# SCH_Meshtastic_FakeTec_PCB_2025-07-15.net
KiCad netlist of a schematic drawn in EasyEDA
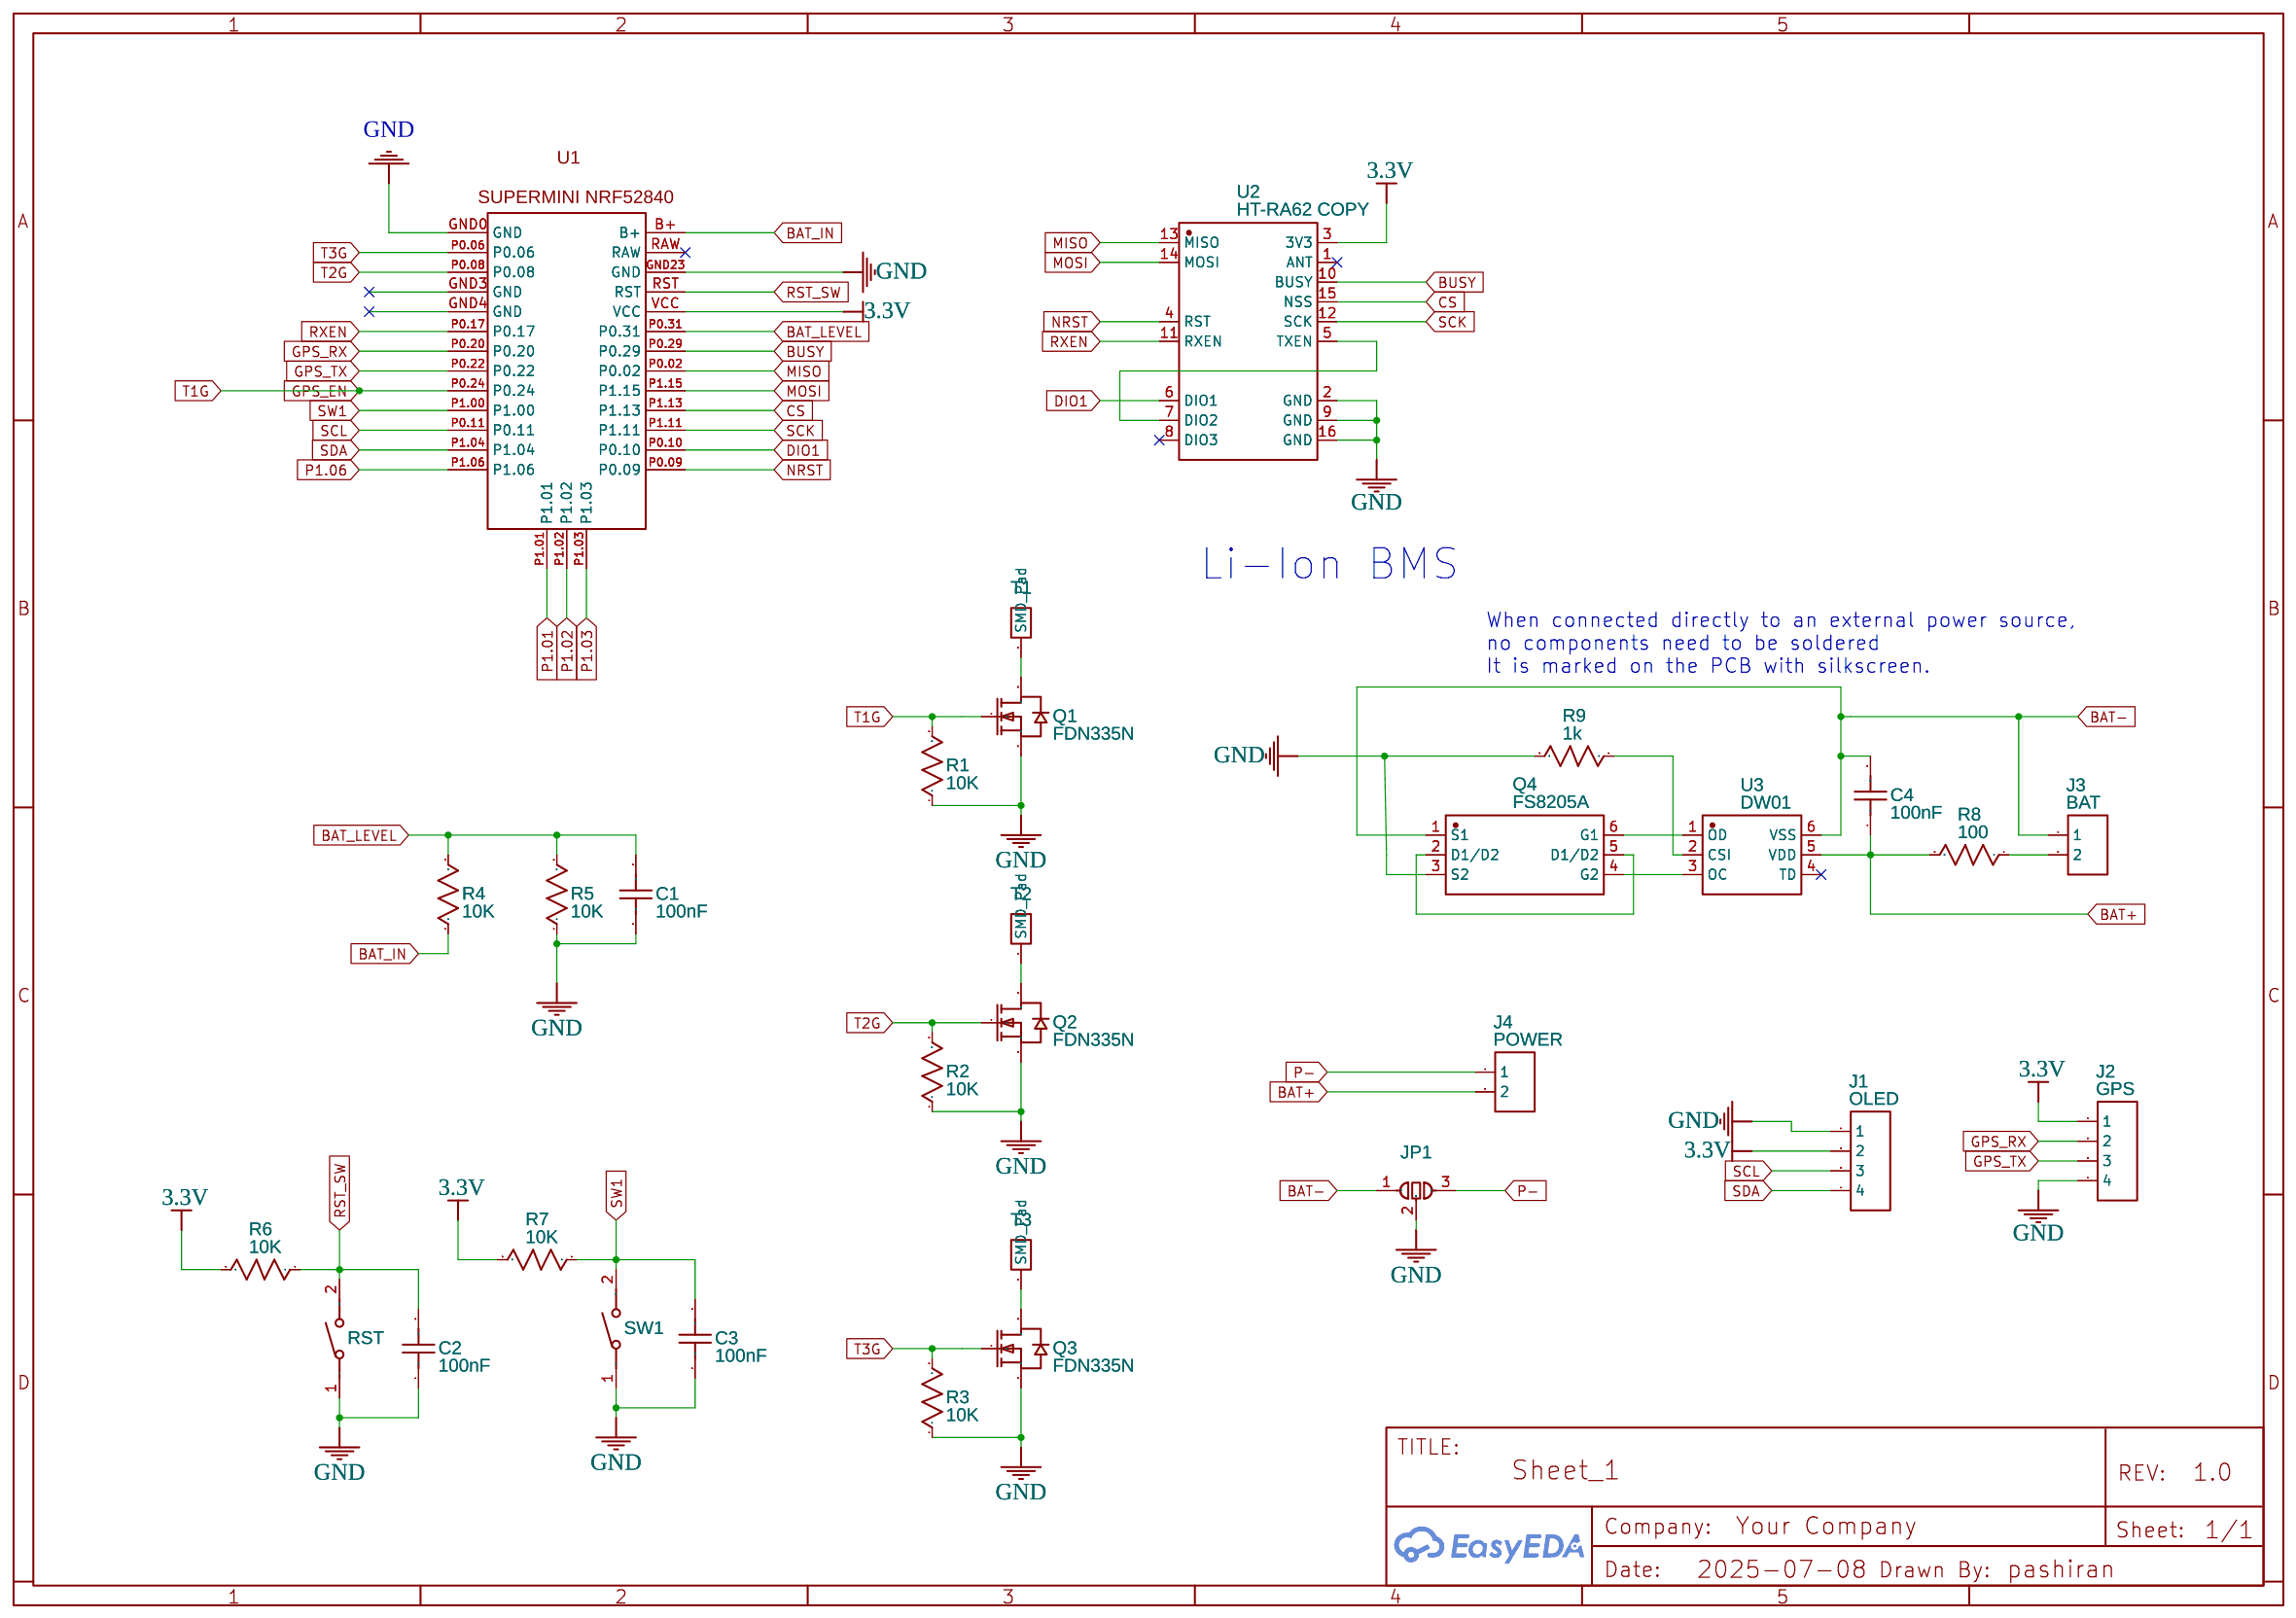
[diagram p0: schematic sheet]

(export (version "E")
  (design (tool "Eeschema 10.0.6"))
  (components
    (comp (ref "C1") (value "100nF") (libsource (lib "") (part "C_0805_US")))
    (comp (ref "C2") (value "100nF") (libsource (lib "") (part "C_0805_US")))
    (comp (ref "C3") (value "100nF") (libsource (lib "") (part "C_0805_US")))
    (comp (ref "C4") (value "100nF") (libsource (lib "") (part "C_0805_US")))
    (comp (ref "J1") (value "OLED") (libsource (lib "") (part "HDR-M-2.54_1x4")))
    (comp (ref "J2") (value "GPS") (libsource (lib "") (part "HDR-M-2.54_1x4")))
    (comp (ref "J3") (value "BAT") (libsource (lib "") (part "HDR-M-2.54_1x2")))
    (comp (ref "J4") (value "POWER") (libsource (lib "") (part "HDR-M-2.54_1x2")))
    (comp (ref "JP1") (value "SOLDERJUMPER_3") (libsource (lib "") (part "SOLDERJUMPER_3")))
    (comp (ref "Q1")
      (value "FDN335N")
      (fields (field (name "Manufacturer") "TECH PUBLIC(台舟)"))
      (libsource (lib "") (part "FDN335N_C5123904"))
    )
    (comp (ref "Q2")
      (value "FDN335N")
      (fields (field (name "Manufacturer") "TECH PUBLIC(台舟)"))
      (libsource (lib "") (part "FDN335N_C5123904"))
    )
    (comp (ref "Q3")
      (value "FDN335N")
      (fields (field (name "Manufacturer") "TECH PUBLIC(台舟)"))
      (libsource (lib "") (part "FDN335N_C5123904"))
    )
    (comp (ref "Q4")
      (value "FS8205A")
      (fields (field (name "Manufacturer") "TECH PUBLIC(台舟)"))
      (libsource (lib "") (part "FS8205A_C2830320"))
    )
    (comp (ref "R1") (value "10K") (libsource (lib "") (part "R_0805_US")))
    (comp (ref "R2") (value "10K") (libsource (lib "") (part "R_0805_US")))
    (comp (ref "R3") (value "10K") (libsource (lib "") (part "R_0805_US")))
    (comp (ref "R4") (value "10K") (libsource (lib "") (part "R_0805_US")))
    (comp (ref "R5") (value "10K") (libsource (lib "") (part "R_0805_US")))
    (comp (ref "R6") (value "10K") (libsource (lib "") (part "R_0805_US_1")))
    (comp (ref "R7") (value "10K") (libsource (lib "") (part "R_0805_US_1")))
    (comp (ref "R8") (value "100") (libsource (lib "") (part "R_0805_US_1")))
    (comp (ref "R9") (value "1k") (libsource (lib "") (part "R_0805_US_1")))
    (comp (ref "RST")
      (value "TS-1088-AR02016")
      (fields (field (name "Manufacturer") "XUNPU(讯普)"))
      (libsource (lib "") (part "TS-1088-AR02016_1"))
    )
    (comp (ref "SW1")
      (value "TS-1088-AR02016")
      (fields (field (name "Manufacturer") "XUNPU(讯普)"))
      (libsource (lib "") (part "TS-1088-AR02016"))
    )
    (comp (ref "T1") (value "SMD_PAD") (libsource (lib "") (part "SMD_PAD")))
    (comp (ref "T2") (value "SMD_PAD") (libsource (lib "") (part "SMD_PAD")))
    (comp (ref "T3") (value "SMD_PAD") (libsource (lib "") (part "SMD_PAD")))
    (comp (ref "U1") (value "SUPERMINI_NRF52840 COPY") (libsource (lib "") (part "SUPERMINI_NRF52840 COPY")))
    (comp (ref "U2")
      (value "HT-RA62 COPY")
      (fields (field (name "Manufacturer Part") "HT-RA62"))
      (libsource (lib "") (part "HT-RA62 COPY"))
    )
    (comp (ref "U3")
      (value "DW01")
      (fields (field (name "Manufacturer") "JSMSEMI(杰盛微)"))
      (libsource (lib "") (part "DW01_C917079"))
    )
  )
  (nets
    (net (code "1") (name "3.3V") (class "Default")
      (node (ref "J1") (pin "2") (pinfunction "2_2") (pintype "unspecified"))
      (node (ref "J2") (pin "1") (pinfunction "1_1") (pintype "unspecified"))
      (node (ref "R6") (pin "2") (pinfunction "2_2") (pintype "unspecified"))
      (node (ref "R7") (pin "2") (pinfunction "2_2") (pintype "unspecified"))
      (node (ref "U1") (pin "VCC") (pinfunction "VCC_VCC") (pintype "bidirectional"))
      (node (ref "U2") (pin "3") (pinfunction "3V3_3") (pintype "unspecified"))
    )
    (net (code "2") (name "BAT+") (class "Default")
      (node (ref "C4") (pin "1") (pinfunction "1_1") (pintype "unspecified"))
      (node (ref "J4") (pin "2") (pinfunction "2_2") (pintype "unspecified"))
      (node (ref "R8") (pin "2") (pinfunction "2_2") (pintype "unspecified"))
      (node (ref "U3") (pin "5") (pinfunction "VDD_5") (pintype "unspecified"))
    )
    (net (code "3") (name "BAT-") (class "Default")
      (node (ref "C4") (pin "2") (pinfunction "2_2") (pintype "unspecified"))
      (node (ref "J3") (pin "1") (pinfunction "1_1") (pintype "unspecified"))
      (node (ref "JP1") (pin "1") (pinfunction "A_1") (pintype "unspecified"))
      (node (ref "Q4") (pin "1") (pinfunction "S1_1") (pintype "unspecified"))
      (node (ref "U3") (pin "6") (pinfunction "VSS_6") (pintype "unspecified"))
    )
    (net (code "4") (name "BAT_IN") (class "Default")
      (node (ref "R4") (pin "1") (pinfunction "1_1") (pintype "unspecified"))
      (node (ref "U1") (pin "B+") (pinfunction "B+_B+") (pintype "bidirectional"))
    )
    (net (code "5") (name "BAT_LEVEL") (class "Default")
      (node (ref "C1") (pin "2") (pinfunction "2_2") (pintype "unspecified"))
      (node (ref "R4") (pin "2") (pinfunction "2_2") (pintype "unspecified"))
      (node (ref "R5") (pin "2") (pinfunction "2_2") (pintype "unspecified"))
      (node (ref "U1") (pin "P0.31") (pinfunction "P0.31_P0.31") (pintype "bidirectional"))
    )
    (net (code "6") (name "BUSY") (class "Default")
      (node (ref "U1") (pin "P0.29") (pinfunction "P0.29_P0.29") (pintype "bidirectional"))
      (node (ref "U2") (pin "10") (pinfunction "BUSY_10") (pintype "unspecified"))
    )
    (net (code "7") (name "CS") (class "Default")
      (node (ref "U1") (pin "P1.13") (pinfunction "P1.13_P1.13") (pintype "bidirectional"))
      (node (ref "U2") (pin "15") (pinfunction "NSS_15") (pintype "unspecified"))
    )
    (net (code "8") (name "DIO1") (class "Default")
      (node (ref "U1") (pin "P0.10") (pinfunction "P0.10_P0.10") (pintype "bidirectional"))
      (node (ref "U2") (pin "6") (pinfunction "DIO1_6") (pintype "unspecified"))
    )
    (net (code "9") (name "GND") (class "Default")
      (node (ref "C1") (pin "1") (pinfunction "1_1") (pintype "unspecified"))
      (node (ref "C2") (pin "1") (pinfunction "1_1") (pintype "unspecified"))
      (node (ref "C3") (pin "1") (pinfunction "1_1") (pintype "unspecified"))
      (node (ref "J1") (pin "1") (pinfunction "1_1") (pintype "unspecified"))
      (node (ref "J2") (pin "4") (pinfunction "4_4") (pintype "unspecified"))
      (node (ref "JP1") (pin "2") (pinfunction "C_2") (pintype "unspecified"))
      (node (ref "Q1") (pin "2") (pinfunction "S_2") (pintype "unspecified"))
      (node (ref "Q2") (pin "2") (pinfunction "S_2") (pintype "unspecified"))
      (node (ref "Q3") (pin "2") (pinfunction "S_2") (pintype "unspecified"))
      (node (ref "Q4") (pin "3") (pinfunction "S2_3") (pintype "unspecified"))
      (node (ref "R1") (pin "1") (pinfunction "1_1") (pintype "unspecified"))
      (node (ref "R2") (pin "1") (pinfunction "1_1") (pintype "unspecified"))
      (node (ref "R3") (pin "1") (pinfunction "1_1") (pintype "unspecified"))
      (node (ref "R5") (pin "1") (pinfunction "1_1") (pintype "unspecified"))
      (node (ref "R9") (pin "2") (pinfunction "2_2") (pintype "unspecified"))
      (node (ref "RST") (pin "1") (pinfunction "1_1") (pintype "unspecified"))
      (node (ref "SW1") (pin "1") (pinfunction "1_1") (pintype "unspecified"))
      (node (ref "U1") (pin "GND0") (pinfunction "GND_GND0") (pintype "unspecified"))
      (node (ref "U1") (pin "GND23") (pinfunction "GND_GND23") (pintype "bidirectional"))
      (node (ref "U2") (pin "16") (pinfunction "GND_16") (pintype "unspecified"))
      (node (ref "U2") (pin "2") (pinfunction "GND_2") (pintype "unspecified"))
      (node (ref "U2") (pin "9") (pinfunction "GND_9") (pintype "unspecified"))
    )
    (net (code "10") (name "GPS_EN") (class "Default")
      (node (ref "Q1") (pin "1") (pinfunction "G_1") (pintype "unspecified"))
      (node (ref "R1") (pin "2") (pinfunction "2_2") (pintype "unspecified"))
      (node (ref "U1") (pin "P0.24") (pinfunction "P0.24_P0.24") (pintype "unspecified"))
    )
    (net (code "11") (name "GPS_RX") (class "Default")
      (node (ref "J2") (pin "2") (pinfunction "2_2") (pintype "unspecified"))
      (node (ref "U1") (pin "P0.20") (pinfunction "P0.20_P0.20") (pintype "unspecified"))
    )
    (net (code "12") (name "GPS_TX") (class "Default")
      (node (ref "J2") (pin "3") (pinfunction "3_3") (pintype "unspecified"))
      (node (ref "U1") (pin "P0.22") (pinfunction "P0.22_P0.22") (pintype "unspecified"))
    )
    (net (code "13") (name "MISO") (class "Default")
      (node (ref "U1") (pin "P0.02") (pinfunction "P0.02_P0.02") (pintype "bidirectional"))
      (node (ref "U2") (pin "13") (pinfunction "MISO_13") (pintype "unspecified"))
    )
    (net (code "14") (name "MOSI") (class "Default")
      (node (ref "U1") (pin "P1.15") (pinfunction "P1.15_P1.15") (pintype "bidirectional"))
      (node (ref "U2") (pin "14") (pinfunction "MOSI_14") (pintype "unspecified"))
    )
    (net (code "15") (name "NRST") (class "Default")
      (node (ref "U1") (pin "P0.09") (pinfunction "P0.09_P0.09") (pintype "bidirectional"))
      (node (ref "U2") (pin "4") (pinfunction "RST_4") (pintype "unspecified"))
    )
    (net (code "16") (name "Net-(J3-Pad2)") (class "Default")
      (node (ref "J3") (pin "2") (pinfunction "2_2") (pintype "unspecified"))
      (node (ref "R8") (pin "1") (pinfunction "1_1") (pintype "unspecified"))
    )
    (net (code "17") (name "Net-(Q1-D)") (class "Default")
      (node (ref "Q1") (pin "3") (pinfunction "D_3") (pintype "unspecified"))
      (node (ref "T1") (pin "1") (pinfunction "SMD_Pad_1") (pintype "unspecified"))
    )
    (net (code "18") (name "Net-(Q2-D)") (class "Default")
      (node (ref "Q2") (pin "3") (pinfunction "D_3") (pintype "unspecified"))
      (node (ref "T2") (pin "1") (pinfunction "SMD_Pad_1") (pintype "unspecified"))
    )
    (net (code "19") (name "Net-(Q3-D)") (class "Default")
      (node (ref "Q3") (pin "3") (pinfunction "D_3") (pintype "unspecified"))
      (node (ref "T3") (pin "1") (pinfunction "SMD_Pad_1") (pintype "unspecified"))
    )
    (net (code "20") (name "Net-(Q4-D1{slash}D2-Pad2)") (class "Default")
      (node (ref "Q4") (pin "2") (pinfunction "D1/D2_2") (pintype "unspecified"))
      (node (ref "Q4") (pin "5") (pinfunction "D1/D2_5") (pintype "unspecified"))
    )
    (net (code "21") (name "Net-(Q4-G1)") (class "Default")
      (node (ref "Q4") (pin "6") (pinfunction "G1_6") (pintype "unspecified"))
      (node (ref "U3") (pin "1") (pinfunction "OD_1") (pintype "unspecified"))
    )
    (net (code "22") (name "Net-(Q4-G2)") (class "Default")
      (node (ref "Q4") (pin "4") (pinfunction "G2_4") (pintype "unspecified"))
      (node (ref "U3") (pin "3") (pinfunction "OC_3") (pintype "unspecified"))
    )
    (net (code "23") (name "Net-(U2-DIO2)") (class "Default")
      (node (ref "U2") (pin "5") (pinfunction "TXEN_5") (pintype "unspecified"))
      (node (ref "U2") (pin "7") (pinfunction "DIO2_7") (pintype "unspecified"))
    )
    (net (code "24") (name "Net-(U3-CSI)") (class "Default")
      (node (ref "R9") (pin "1") (pinfunction "1_1") (pintype "unspecified"))
      (node (ref "U3") (pin "2") (pinfunction "CSI_2") (pintype "unspecified"))
    )
    (net (code "25") (name "P-") (class "Default")
      (node (ref "J4") (pin "1") (pinfunction "1_1") (pintype "unspecified"))
      (node (ref "JP1") (pin "3") (pinfunction "B_3") (pintype "unspecified"))
    )
    (net (code "26") (name "P1.01") (class "Default")
      (node (ref "U1") (pin "P1.01") (pinfunction "P1.01_P1.01") (pintype "unspecified"))
    )
    (net (code "27") (name "P1.02") (class "Default")
      (node (ref "U1") (pin "P1.02") (pinfunction "P1.02_P1.02") (pintype "unspecified"))
    )
    (net (code "28") (name "P1.03") (class "Default")
      (node (ref "U1") (pin "P1.03") (pinfunction "P1.03_P1.03") (pintype "unspecified"))
    )
    (net (code "29") (name "P1.06") (class "Default")
      (node (ref "U1") (pin "P1.06") (pinfunction "P1.06_P1.06") (pintype "unspecified"))
    )
    (net (code "30") (name "RST_SW") (class "Default")
      (node (ref "C2") (pin "2") (pinfunction "2_2") (pintype "unspecified"))
      (node (ref "R6") (pin "1") (pinfunction "1_1") (pintype "unspecified"))
      (node (ref "RST") (pin "2") (pinfunction "2_2") (pintype "unspecified"))
      (node (ref "U1") (pin "RST") (pinfunction "RST_RST") (pintype "bidirectional"))
    )
    (net (code "31") (name "RXEN") (class "Default")
      (node (ref "U1") (pin "P0.17") (pinfunction "P0.17_P0.17") (pintype "unspecified"))
      (node (ref "U2") (pin "11") (pinfunction "RXEN_11") (pintype "unspecified"))
    )
    (net (code "32") (name "SCK") (class "Default")
      (node (ref "U1") (pin "P1.11") (pinfunction "P1.11_P1.11") (pintype "bidirectional"))
      (node (ref "U2") (pin "12") (pinfunction "SCK_12") (pintype "unspecified"))
    )
    (net (code "33") (name "SCL") (class "Default")
      (node (ref "J1") (pin "3") (pinfunction "3_3") (pintype "unspecified"))
      (node (ref "U1") (pin "P0.11") (pinfunction "P0.11_P0.11") (pintype "unspecified"))
    )
    (net (code "34") (name "SDA") (class "Default")
      (node (ref "J1") (pin "4") (pinfunction "4_4") (pintype "unspecified"))
      (node (ref "U1") (pin "P1.04") (pinfunction "P1.04_P1.04") (pintype "unspecified"))
    )
    (net (code "35") (name "SW1") (class "Default")
      (node (ref "C3") (pin "2") (pinfunction "2_2") (pintype "unspecified"))
      (node (ref "R7") (pin "1") (pinfunction "1_1") (pintype "unspecified"))
      (node (ref "SW1") (pin "2") (pinfunction "2_2") (pintype "unspecified"))
      (node (ref "U1") (pin "P1.00") (pinfunction "P1.00_P1.00") (pintype "unspecified"))
    )
    (net (code "36") (name "T2G") (class "Default")
      (node (ref "Q2") (pin "1") (pinfunction "G_1") (pintype "unspecified"))
      (node (ref "R2") (pin "2") (pinfunction "2_2") (pintype "unspecified"))
      (node (ref "U1") (pin "P0.08") (pinfunction "P0.08_P0.08") (pintype "input"))
    )
    (net (code "37") (name "T3G") (class "Default")
      (node (ref "Q3") (pin "1") (pinfunction "G_1") (pintype "unspecified"))
      (node (ref "R3") (pin "2") (pinfunction "2_2") (pintype "unspecified"))
      (node (ref "U1") (pin "P0.06") (pinfunction "P0.06_P0.06") (pintype "unspecified"))
    )
    (net (code "38") (name "unconnected-(U1-GND-PadGND3)") (class "Default")
      (node (ref "U1") (pin "GND3") (pinfunction "GND_GND3") (pintype "unspecified+no_connect"))
    )
    (net (code "39") (name "unconnected-(U1-GND-PadGND4)") (class "Default")
      (node (ref "U1") (pin "GND4") (pinfunction "GND_GND4") (pintype "unspecified+no_connect"))
    )
    (net (code "40") (name "unconnected-(U1-PadRAW)") (class "Default")
      (node (ref "U1") (pin "RAW") (pinfunction "RAW_RAW") (pintype "bidirectional+no_connect"))
    )
    (net (code "41") (name "unconnected-(U2-ANT-Pad1)") (class "Default")
      (node (ref "U2") (pin "1") (pinfunction "ANT_1") (pintype "unspecified+no_connect"))
    )
    (net (code "42") (name "unconnected-(U2-DIO3-Pad8)") (class "Default")
      (node (ref "U2") (pin "8") (pinfunction "DIO3_8") (pintype "unspecified+no_connect"))
    )
    (net (code "43") (name "unconnected-(U3-TD-Pad4)") (class "Default")
      (node (ref "U3") (pin "4") (pinfunction "TD_4") (pintype "unspecified+no_connect"))
    )
  )
)
